# MosfetDrive.net
KiCad netlist of a schematic drawn in Altium Designer
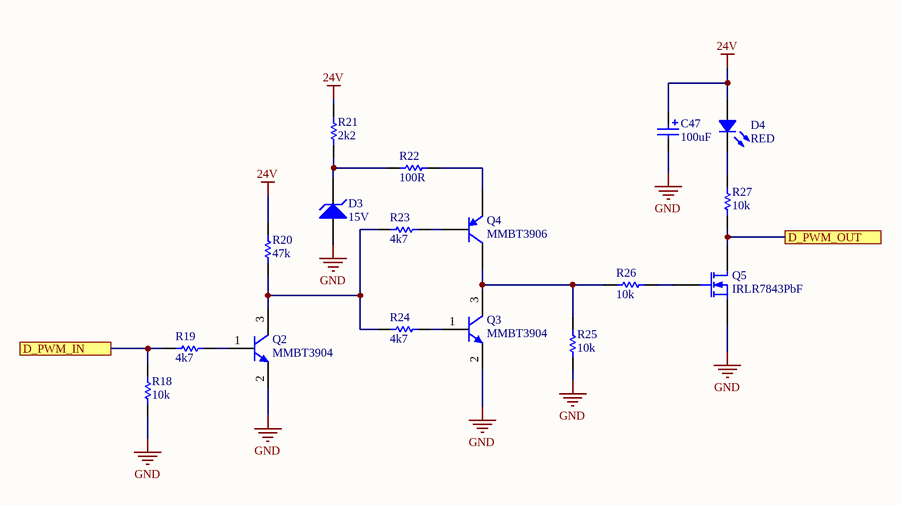
[diagram p0: MosfetDrive.SchDoc]

(export (version "E")
  (design (tool "Eeschema 10.0.6"))
  (components
    (comp (ref "C47")
      (value "100uF")
      (footprint "TAN-B")
      (description "Polarized Capacitor (Radial)")
      (fields (field (name "PUBLISHER") "Altium Limited"))
      (libsource (lib "MB1137") (part "Cap Pol1"))
    )
    (comp (ref "D3")
      (value "15V")
      (footprint "DIODE-0.7")
      (description "Zener Diode")
      (fields (field (name "PUBLISHER") "Altium Limited"))
      (libsource (lib "Miscellaneous Devices") (part "D Zener"))
    )
    (comp (ref "D4")
      (value "RED")
      (footprint "Broadcom 4-PLLC 3228")
      (description "LED INDICATOR 0.5W AMBER 4PLCC")
      (fields (field (name "PART NUMBER") "ASMT-QABD-AEF0E") (field (name "MANUFACTURER") "Broadcom Limited"))
      (libsource (lib "Celestial Altium Library - altium_library") (part "LED"))
    )
    (comp (ref "Q2")
      (value "MMBT3904")
      (footprint "ON SEMICONDUCTOR SC-75")
      (description "TRANS NPN 40V 0.2A SOT416")
      (fields (field (name "PART NUMBER") "MMBT3904TT1G") (field (name "MANUFACTURER") "ON Semiconductor"))
      (libsource (lib "Celestial Altium Library - altium_library") (part "ON SEMI NPN SC-75"))
    )
    (comp (ref "Q3")
      (value "MMBT3904")
      (footprint "ON SEMICONDUCTOR SC-75")
      (description "TRANS NPN 40V 0.2A SOT416")
      (fields (field (name "PART NUMBER") "MMBT3904TT1G") (field (name "MANUFACTURER") "ON Semiconductor"))
      (libsource (lib "Celestial Altium Library - altium_library") (part "ON SEMI NPN SC-75"))
    )
    (comp (ref "Q4")
      (value "MMBT3906")
      (footprint "TO-92A")
      (description "PNP General Purpose Amplifier")
      (fields (field (name "PUBLISHER") "Altium Limited"))
      (libsource (lib "Miscellaneous Devices") (part "2N3906"))
    )
    (comp (ref "Q5")
      (value "IRLR7843PbF")
      (footprint "E3")
      (description "N-Channel MOSFET")
      (fields (field (name "PUBLISHER") "Altium Limited"))
      (libsource (lib "Miscellaneous Devices") (part "MOSFET-N"))
    )
    (comp (ref "R18")
      (value "10k")
      (footprint "AXIAL-0.3")
      (description "Resistor")
      (fields (field (name "Comment") "Res1") (field (name "PUBLISHER") "Altium Limited"))
      (libsource (lib "Miscellaneous Devices") (part "Res1"))
    )
    (comp (ref "R19")
      (value "4k7")
      (footprint "AXIAL-0.3")
      (description "Resistor")
      (fields (field (name "Comment") "Res1") (field (name "PUBLISHER") "Altium Limited"))
      (libsource (lib "Miscellaneous Devices") (part "Res1"))
    )
    (comp (ref "R20")
      (value "47k")
      (footprint "AXIAL-0.3")
      (description "Resistor")
      (fields (field (name "Comment") "Res1") (field (name "PUBLISHER") "Altium Limited"))
      (libsource (lib "Miscellaneous Devices") (part "Res1"))
    )
    (comp (ref "R21")
      (value "2k2")
      (footprint "AXIAL-0.3")
      (description "Resistor")
      (fields (field (name "Comment") "Res1") (field (name "PUBLISHER") "Altium Limited"))
      (libsource (lib "Miscellaneous Devices") (part "Res1"))
    )
    (comp (ref "R22")
      (value "100R")
      (footprint "AXIAL-0.3")
      (description "Resistor")
      (fields (field (name "Comment") "Res1") (field (name "PUBLISHER") "Altium Limited"))
      (libsource (lib "Miscellaneous Devices") (part "Res1"))
    )
    (comp (ref "R23")
      (value "4k7")
      (footprint "AXIAL-0.3")
      (description "Resistor")
      (fields (field (name "Comment") "Res1") (field (name "PUBLISHER") "Altium Limited"))
      (libsource (lib "Miscellaneous Devices") (part "Res1"))
    )
    (comp (ref "R24")
      (value "4k7")
      (footprint "AXIAL-0.3")
      (description "Resistor")
      (fields (field (name "Comment") "Res1") (field (name "PUBLISHER") "Altium Limited"))
      (libsource (lib "Miscellaneous Devices") (part "Res1"))
    )
    (comp (ref "R25")
      (value "10k")
      (footprint "AXIAL-0.3")
      (description "Resistor")
      (fields (field (name "Comment") "Res1") (field (name "PUBLISHER") "Altium Limited"))
      (libsource (lib "Miscellaneous Devices") (part "Res1"))
    )
    (comp (ref "R26")
      (value "10k")
      (footprint "AXIAL-0.3")
      (description "Resistor")
      (fields (field (name "Comment") "Res1") (field (name "PUBLISHER") "Altium Limited"))
      (libsource (lib "Miscellaneous Devices") (part "Res1"))
    )
    (comp (ref "R27")
      (value "10k")
      (footprint "AXIAL-0.3")
      (description "Resistor")
      (fields (field (name "Comment") "Res1") (field (name "PUBLISHER") "Altium Limited"))
      (libsource (lib "Miscellaneous Devices") (part "Res1"))
    )
  )
  (nets
    (net (code "1") (name "/D_PWM_IN") (class "Default")
      (node (ref "R18") (pin "2") (pinfunction "2_2") (pintype "passive"))
      (node (ref "R19") (pin "1") (pinfunction "1_1") (pintype "passive"))
    )
    (net (code "2") (name "/D_PWM_OUT") (class "Default")
      (node (ref "Q5") (pin "1") (pinfunction "D_1") (pintype "passive"))
      (node (ref "R27") (pin "1") (pinfunction "1_1") (pintype "passive"))
    )
    (net (code "3") (name "24V") (class "Default")
      (node (ref "C47") (pin "1") (pinfunction "1_1") (pintype "passive"))
      (node (ref "D4") (pin "1") (pinfunction "1_1") (pintype "passive"))
      (node (ref "R20") (pin "2") (pinfunction "2_2") (pintype "passive"))
      (node (ref "R21") (pin "2") (pinfunction "2_2") (pintype "passive"))
    )
    (net (code "4") (name "GND") (class "Default")
      (node (ref "C47") (pin "2") (pinfunction "2_2") (pintype "passive"))
      (node (ref "D3") (pin "1") (pinfunction "A_1") (pintype "passive"))
      (node (ref "Q2") (pin "2") (pinfunction "E_2") (pintype "passive"))
      (node (ref "Q3") (pin "2") (pinfunction "E_2") (pintype "passive"))
      (node (ref "Q5") (pin "3") (pinfunction "S_3") (pintype "passive"))
      (node (ref "R18") (pin "1") (pinfunction "1_1") (pintype "passive"))
      (node (ref "R25") (pin "1") (pinfunction "1_1") (pintype "passive"))
    )
    (net (code "5") (name "Net-(D3-K)") (class "Default")
      (node (ref "D3") (pin "2") (pinfunction "K_2") (pintype "passive"))
      (node (ref "R21") (pin "1") (pinfunction "1_1") (pintype "passive"))
      (node (ref "R22") (pin "2") (pinfunction "2_2") (pintype "passive"))
    )
    (net (code "6") (name "Net-(D4-Pad2)") (class "Default")
      (node (ref "D4") (pin "2") (pinfunction "2_2") (pintype "passive"))
      (node (ref "R27") (pin "2") (pinfunction "2_2") (pintype "passive"))
    )
    (net (code "7") (name "Net-(Q2-B)") (class "Default")
      (node (ref "Q2") (pin "1") (pinfunction "B_1") (pintype "passive"))
      (node (ref "R19") (pin "2") (pinfunction "2_2") (pintype "passive"))
    )
    (net (code "8") (name "Net-(Q2-C)") (class "Default")
      (node (ref "Q2") (pin "3") (pinfunction "C_3") (pintype "passive"))
      (node (ref "R20") (pin "1") (pinfunction "1_1") (pintype "passive"))
      (node (ref "R23") (pin "1") (pinfunction "1_1") (pintype "passive"))
      (node (ref "R24") (pin "1") (pinfunction "1_1") (pintype "passive"))
    )
    (net (code "9") (name "Net-(Q3-B)") (class "Default")
      (node (ref "Q3") (pin "1") (pinfunction "B_1") (pintype "passive"))
      (node (ref "R24") (pin "2") (pinfunction "2_2") (pintype "passive"))
    )
    (net (code "10") (name "Net-(Q3-C)") (class "Default")
      (node (ref "Q3") (pin "3") (pinfunction "C_3") (pintype "passive"))
      (node (ref "Q4") (pin "3") (pinfunction "C_3") (pintype "passive"))
      (node (ref "R25") (pin "2") (pinfunction "2_2") (pintype "passive"))
      (node (ref "R26") (pin "1") (pinfunction "1_1") (pintype "passive"))
    )
    (net (code "11") (name "Net-(Q4-B)") (class "Default")
      (node (ref "Q4") (pin "2") (pinfunction "B_2") (pintype "passive"))
      (node (ref "R23") (pin "2") (pinfunction "2_2") (pintype "passive"))
    )
    (net (code "12") (name "Net-(Q4-E)") (class "Default")
      (node (ref "Q4") (pin "1") (pinfunction "E_1") (pintype "passive"))
      (node (ref "R22") (pin "1") (pinfunction "1_1") (pintype "passive"))
    )
    (net (code "13") (name "Net-(Q5-G)") (class "Default")
      (node (ref "Q5") (pin "2") (pinfunction "G_2") (pintype "passive"))
      (node (ref "R26") (pin "2") (pinfunction "2_2") (pintype "passive"))
    )
  )
)
